# tira_rev4.net
KiCad netlist of a schematic drawn in EAGLE
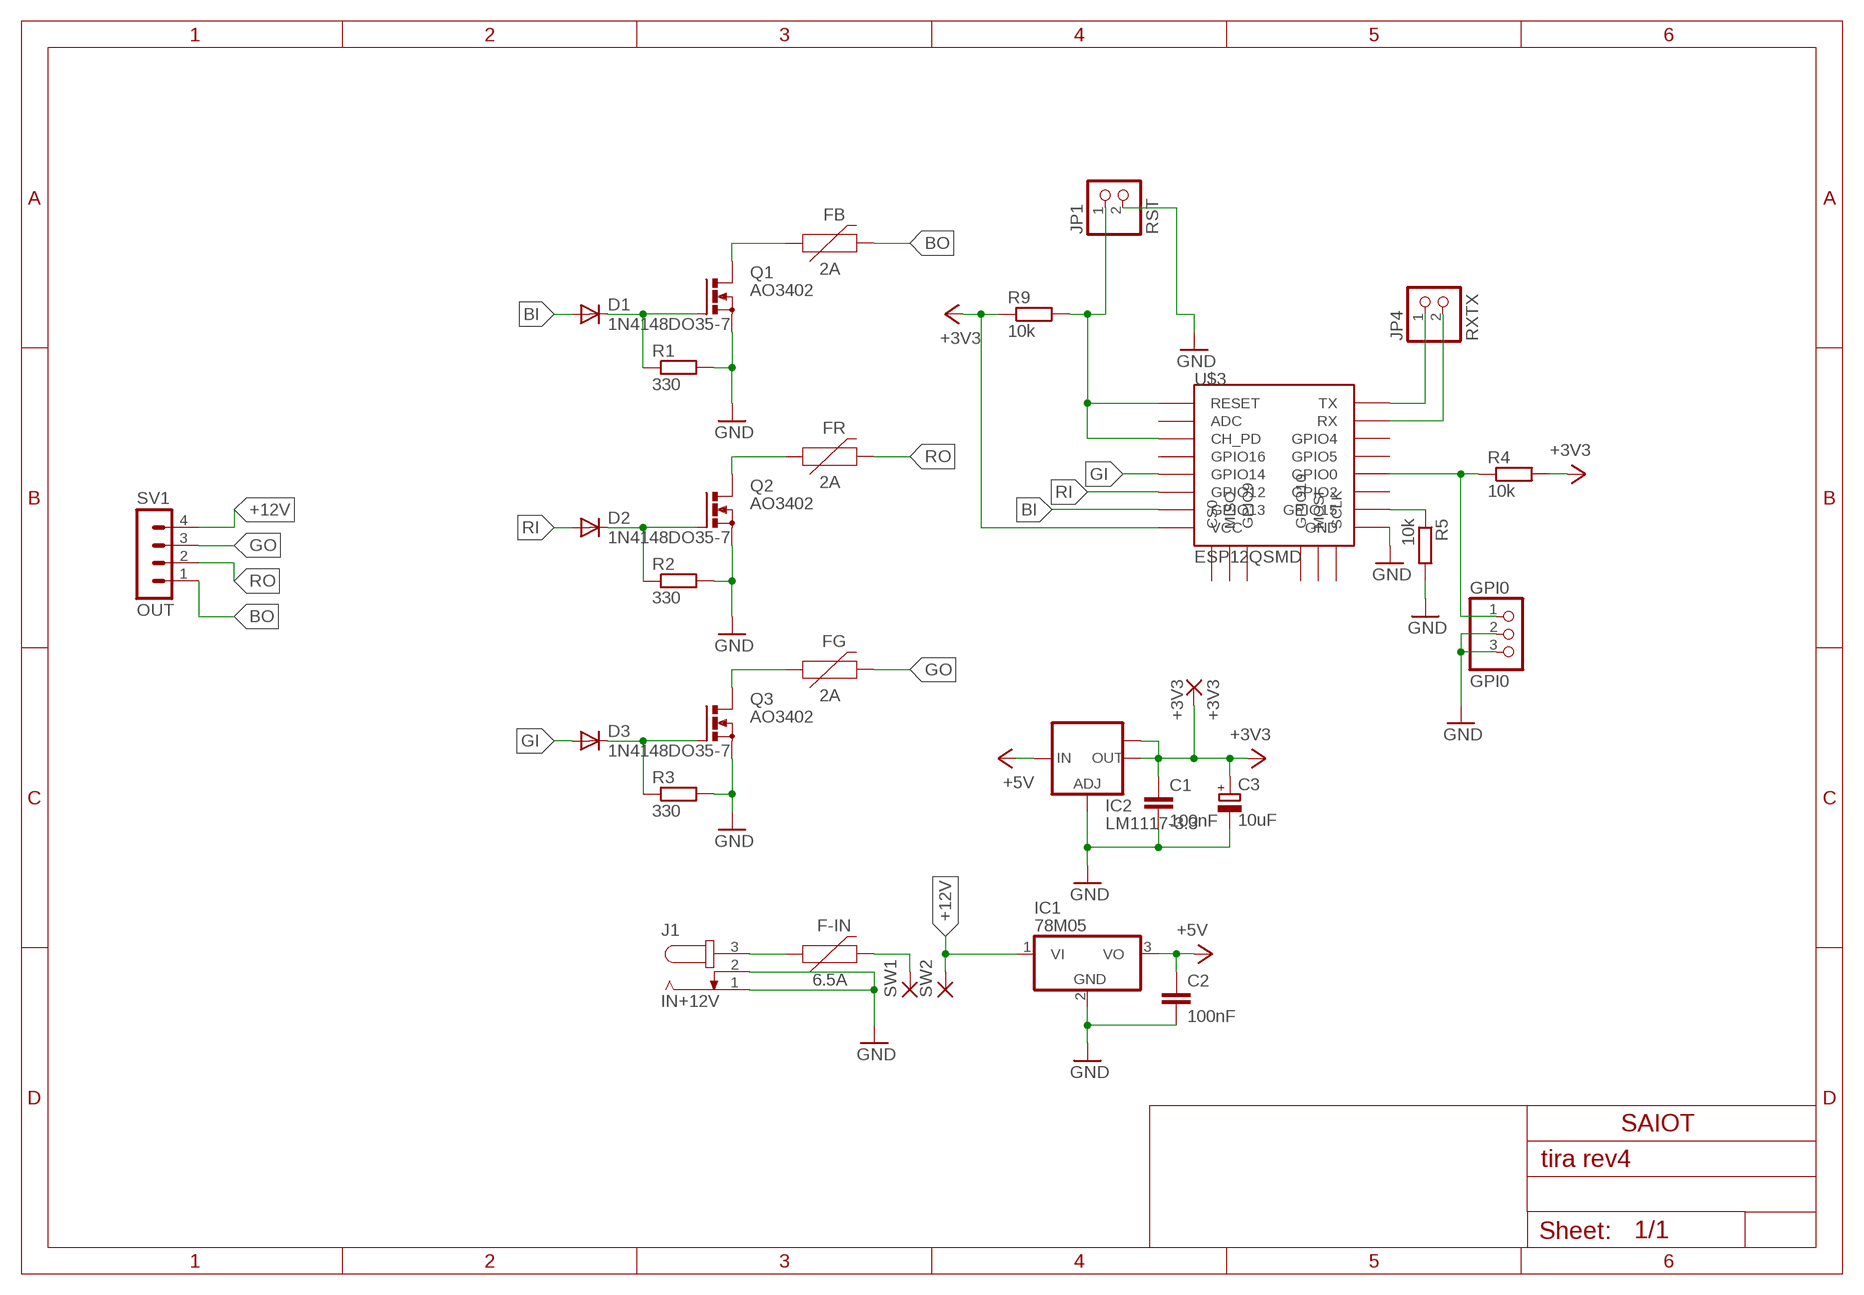
[diagram p0: schematic, sheet 1]

(export (version "E")
  (design (tool "Eeschema 10.0.6"))
  (components
    (comp (ref "+3V3")
      (value "+3V3")
      (footprint "eagle-import:2,15_1,0")
      (libsource (lib "eagle-import") (part "2,15/1,0"))
    )
    (comp (ref "C1")
      (value "100nF")
      (footprint "eagle-import:C050-024X044")
      (libsource (lib "eagle-import") (part "C-EU050-024X044"))
    )
    (comp (ref "C2")
      (value "100nF")
      (footprint "eagle-import:C050-024X044")
      (libsource (lib "eagle-import") (part "C-EU050-024X044"))
    )
    (comp (ref "C3")
      (value "10uF")
      (footprint "eagle-import:E2,5-7")
      (libsource (lib "eagle-import") (part "CPOL-EUE2.5-7"))
    )
    (comp (ref "D1")
      (value "1N4148DO35-7")
      (footprint "eagle-import:DO35-7")
      (libsource (lib "eagle-import") (part "1N4148DO35-7"))
    )
    (comp (ref "D2")
      (value "1N4148DO35-7")
      (footprint "eagle-import:DO35-7")
      (libsource (lib "eagle-import") (part "1N4148DO35-7"))
    )
    (comp (ref "D3")
      (value "1N4148DO35-7")
      (footprint "eagle-import:DO35-7")
      (libsource (lib "eagle-import") (part "1N4148DO35-7"))
    )
    (comp (ref "F-IN")
      (value "6.5A")
      (footprint "eagle-import:0805")
      (libsource (lib "eagle-import") (part "PPTC_6V500MA"))
    )
    (comp (ref "FB")
      (value "2A")
      (footprint "eagle-import:0805")
      (libsource (lib "eagle-import") (part "PPTC_6V500MA"))
    )
    (comp (ref "FG")
      (value "2A")
      (footprint "eagle-import:0805")
      (libsource (lib "eagle-import") (part "PPTC_6V500MA"))
    )
    (comp (ref "FR")
      (value "2A")
      (footprint "eagle-import:0805")
      (libsource (lib "eagle-import") (part "PPTC_6V500MA"))
    )
    (comp (ref "GPI0")
      (value "GPI0")
      (footprint "eagle-import:1X03")
      (libsource (lib "eagle-import") (part "PINHD-1X3"))
    )
    (comp (ref "IC1")
      (value "78M05")
      (footprint "eagle-import:TO220H")
      (libsource (lib "eagle-import") (part "78T05"))
    )
    (comp (ref "IC2")
      (value "LM1117-3.3")
      (footprint "eagle-import:SOT223")
      (libsource (lib "eagle-import") (part "LM1117IMPX-ADJ"))
    )
    (comp (ref "J1")
      (value "IN+12V")
      (footprint "eagle-import:SPC4077")
      (libsource (lib "eagle-import") (part "JACK-PLUG0"))
    )
    (comp (ref "JP1")
      (value "RST")
      (footprint "eagle-import:1X02")
      (libsource (lib "eagle-import") (part "PINHD-1X2"))
    )
    (comp (ref "JP4")
      (value "RXTX")
      (footprint "eagle-import:1X02")
      (libsource (lib "eagle-import") (part "PINHD-1X2"))
    )
    (comp (ref "Q1")
      (value "AO3402")
      (footprint "eagle-import:SOT-23")
      (libsource (lib "eagle-import") (part "IRLML6344"))
    )
    (comp (ref "Q2")
      (value "AO3402")
      (footprint "eagle-import:SOT-23")
      (libsource (lib "eagle-import") (part "IRLML6344"))
    )
    (comp (ref "Q3")
      (value "AO3402")
      (footprint "eagle-import:SOT-23")
      (libsource (lib "eagle-import") (part "IRLML6344"))
    )
    (comp (ref "R1")
      (value "330")
      (footprint "eagle-import:0204_7")
      (libsource (lib "eagle-import") (part "R-EU_0204/7"))
    )
    (comp (ref "R2")
      (value "330")
      (footprint "eagle-import:0204_7")
      (libsource (lib "eagle-import") (part "R-EU_0204/7"))
    )
    (comp (ref "R3")
      (value "330")
      (footprint "eagle-import:0204_7")
      (libsource (lib "eagle-import") (part "R-EU_0204/7"))
    )
    (comp (ref "R4")
      (value "10k")
      (footprint "eagle-import:0204_7")
      (libsource (lib "eagle-import") (part "R-EU_0204/7"))
    )
    (comp (ref "R5")
      (value "10k")
      (footprint "eagle-import:0204_7")
      (libsource (lib "eagle-import") (part "R-EU_0204/7"))
    )
    (comp (ref "R9")
      (value "10k")
      (footprint "eagle-import:0204_7")
      (libsource (lib "eagle-import") (part "R-EU_0204/7"))
    )
    (comp (ref "SV1")
      (value "OUT")
      (footprint "eagle-import:MA04-1")
      (libsource (lib "eagle-import") (part "MA04-1"))
    )
    (comp (ref "SW1")
      (value "1,6/0,8")
      (footprint "eagle-import:1,6_0,8")
      (libsource (lib "eagle-import") (part "1,6/0,8"))
    )
    (comp (ref "SW2")
      (value "1,6/0,8")
      (footprint "eagle-import:1,6_0,8")
      (libsource (lib "eagle-import") (part "1,6/0,8"))
    )
    (comp (ref "U$3")
      (value "ESP12QSMD")
      (footprint "eagle-import:ESP12QSMD")
      (libsource (lib "eagle-import") (part "ESP12QSMD"))
    )
  )
  (nets
    (net (code "1") (name "+3V3") (class "Default")
      (node (ref "+3V3") (pin "1") (pinfunction "P_1") (pintype "passive"))
      (node (ref "C1") (pin "1") (pinfunction "1_1") (pintype "passive"))
      (node (ref "C3") (pin "+") (pinfunction "+_+") (pintype "passive"))
      (node (ref "IC2") (pin "2") (pinfunction "OUT_2") (pintype "passive"))
      (node (ref "IC2") (pin "TAB") (pinfunction "OUT1_TAB") (pintype "passive"))
      (node (ref "R4") (pin "2") (pinfunction "2_2") (pintype "passive"))
      (node (ref "R9") (pin "1") (pinfunction "1_1") (pintype "passive"))
      (node (ref "U$3") (pin "VCC") (pinfunction "VCC_VCC") (pintype "bidirectional"))
    )
    (net (code "2") (name "+5V") (class "Default")
      (node (ref "C2") (pin "1") (pinfunction "1_1") (pintype "passive"))
      (node (ref "IC1") (pin "3") (pinfunction "VO_3") (pintype "passive"))
      (node (ref "IC2") (pin "3") (pinfunction "IN_3") (pintype "input"))
    )
    (net (code "3") (name "+12V") (class "Default")
      (node (ref "IC1") (pin "1") (pinfunction "VI_1") (pintype "input"))
      (node (ref "SV1") (pin "4") (pinfunction "4_4") (pintype "passive"))
      (node (ref "SW2") (pin "1") (pinfunction "P_1") (pintype "passive"))
    )
    (net (code "4") (name "BI") (class "Default")
      (node (ref "D1") (pin "A") (pinfunction "A_A") (pintype "passive"))
      (node (ref "U$3") (pin "GPIO13") (pinfunction "GPIO13_GPIO13") (pintype "bidirectional"))
    )
    (net (code "5") (name "BO") (class "Default")
      (node (ref "FB") (pin "2") (pinfunction "2_2") (pintype "bidirectional"))
      (node (ref "SV1") (pin "1") (pinfunction "1_1") (pintype "passive"))
    )
    (net (code "6") (name "GI") (class "Default")
      (node (ref "D3") (pin "A") (pinfunction "A_A") (pintype "passive"))
      (node (ref "U$3") (pin "GPIO14") (pinfunction "GPIO14_GPIO14") (pintype "bidirectional"))
    )
    (net (code "7") (name "GND") (class "Default")
      (node (ref "C1") (pin "2") (pinfunction "2_2") (pintype "passive"))
      (node (ref "C2") (pin "2") (pinfunction "2_2") (pintype "passive"))
      (node (ref "C3") (pin "-") (pinfunction "-_-") (pintype "passive"))
      (node (ref "GPI0") (pin "2") (pinfunction "2_2") (pintype "passive"))
      (node (ref "GPI0") (pin "3") (pinfunction "3_3") (pintype "passive"))
      (node (ref "IC1") (pin "2") (pinfunction "GND_2") (pintype "passive"))
      (node (ref "IC2") (pin "1") (pinfunction "ADJ_1") (pintype "input"))
      (node (ref "J1") (pin "1") (pinfunction "1_1") (pintype "passive"))
      (node (ref "J1") (pin "2") (pinfunction "2_2") (pintype "passive"))
      (node (ref "JP1") (pin "2") (pinfunction "2_2") (pintype "passive"))
      (node (ref "Q1") (pin "P2") (pinfunction "S_P2") (pintype "passive"))
      (node (ref "Q2") (pin "P2") (pinfunction "S_P2") (pintype "passive"))
      (node (ref "Q3") (pin "P2") (pinfunction "S_P2") (pintype "passive"))
      (node (ref "R1") (pin "2") (pinfunction "2_2") (pintype "passive"))
      (node (ref "R2") (pin "2") (pinfunction "2_2") (pintype "passive"))
      (node (ref "R3") (pin "2") (pinfunction "2_2") (pintype "passive"))
      (node (ref "R5") (pin "2") (pinfunction "2_2") (pintype "passive"))
      (node (ref "U$3") (pin "GND") (pinfunction "GND_GND") (pintype "bidirectional"))
    )
    (net (code "8") (name "GO") (class "Default")
      (node (ref "FG") (pin "2") (pinfunction "2_2") (pintype "bidirectional"))
      (node (ref "SV1") (pin "3") (pinfunction "3_3") (pintype "passive"))
    )
    (net (code "9") (name "Net-(F-IN-Pad1)") (class "Default")
      (node (ref "F-IN") (pin "1") (pinfunction "1_1") (pintype "bidirectional"))
      (node (ref "J1") (pin "3") (pinfunction "3_3") (pintype "passive"))
    )
    (net (code "10") (name "Net-(GPI0-Pad1)") (class "Default")
      (node (ref "GPI0") (pin "1") (pinfunction "1_1") (pintype "passive"))
      (node (ref "R4") (pin "1") (pinfunction "1_1") (pintype "passive"))
      (node (ref "U$3") (pin "GPIO0") (pinfunction "GPIO0_GPIO0") (pintype "bidirectional"))
    )
    (net (code "11") (name "Net-(JP1-Pad1)") (class "Default")
      (node (ref "JP1") (pin "1") (pinfunction "1_1") (pintype "passive"))
      (node (ref "R9") (pin "2") (pinfunction "2_2") (pintype "passive"))
      (node (ref "U$3") (pin "CH_PD") (pinfunction "CH_PD_CH_PD") (pintype "bidirectional"))
      (node (ref "U$3") (pin "RESET") (pinfunction "RESET_RESET") (pintype "bidirectional"))
    )
    (net (code "12") (name "Net-(JP4-Pad1)") (class "Default")
      (node (ref "JP4") (pin "1") (pinfunction "1_1") (pintype "passive"))
      (node (ref "U$3") (pin "TX") (pinfunction "TX_TX") (pintype "bidirectional"))
    )
    (net (code "13") (name "Net-(JP4-Pad2)") (class "Default")
      (node (ref "JP4") (pin "2") (pinfunction "2_2") (pintype "passive"))
      (node (ref "U$3") (pin "RX") (pinfunction "RX_RX") (pintype "bidirectional"))
    )
    (net (code "14") (name "Net-(Q1-D)") (class "Default")
      (node (ref "FB") (pin "1") (pinfunction "1_1") (pintype "bidirectional"))
      (node (ref "Q1") (pin "P3") (pinfunction "D_P3") (pintype "passive"))
    )
    (net (code "15") (name "Net-(Q1-G)") (class "Default")
      (node (ref "D1") (pin "C") (pinfunction "C_C") (pintype "passive"))
      (node (ref "Q1") (pin "P1") (pinfunction "G_P1") (pintype "passive"))
      (node (ref "R1") (pin "1") (pinfunction "1_1") (pintype "passive"))
    )
    (net (code "16") (name "Net-(Q2-D)") (class "Default")
      (node (ref "FR") (pin "1") (pinfunction "1_1") (pintype "bidirectional"))
      (node (ref "Q2") (pin "P3") (pinfunction "D_P3") (pintype "passive"))
    )
    (net (code "17") (name "Net-(Q2-G)") (class "Default")
      (node (ref "D2") (pin "C") (pinfunction "C_C") (pintype "passive"))
      (node (ref "Q2") (pin "P1") (pinfunction "G_P1") (pintype "passive"))
      (node (ref "R2") (pin "1") (pinfunction "1_1") (pintype "passive"))
    )
    (net (code "18") (name "Net-(Q3-D)") (class "Default")
      (node (ref "FG") (pin "1") (pinfunction "1_1") (pintype "bidirectional"))
      (node (ref "Q3") (pin "P3") (pinfunction "D_P3") (pintype "passive"))
    )
    (net (code "19") (name "Net-(Q3-G)") (class "Default")
      (node (ref "D3") (pin "C") (pinfunction "C_C") (pintype "passive"))
      (node (ref "Q3") (pin "P1") (pinfunction "G_P1") (pintype "passive"))
      (node (ref "R3") (pin "1") (pinfunction "1_1") (pintype "passive"))
    )
    (net (code "20") (name "Net-(R5-Pad1)") (class "Default")
      (node (ref "R5") (pin "1") (pinfunction "1_1") (pintype "passive"))
      (node (ref "U$3") (pin "GPIO15") (pinfunction "GPIO15_GPIO15") (pintype "bidirectional"))
    )
    (net (code "21") (name "Net-(SW1-P)") (class "Default")
      (node (ref "F-IN") (pin "2") (pinfunction "2_2") (pintype "bidirectional"))
      (node (ref "SW1") (pin "1") (pinfunction "P_1") (pintype "passive"))
    )
    (net (code "22") (name "RI") (class "Default")
      (node (ref "D2") (pin "A") (pinfunction "A_A") (pintype "passive"))
      (node (ref "U$3") (pin "GPIO12") (pinfunction "GPIO12_GPIO12") (pintype "bidirectional"))
    )
    (net (code "23") (name "RO") (class "Default")
      (node (ref "FR") (pin "2") (pinfunction "2_2") (pintype "bidirectional"))
      (node (ref "SV1") (pin "2") (pinfunction "2_2") (pintype "passive"))
    )
    (net (code "24") (name "unconnected-(U$3-PadADC)") (class "Default")
      (node (ref "U$3") (pin "ADC") (pinfunction "ADC_ADC") (pintype "bidirectional"))
    )
    (net (code "25") (name "unconnected-(U$3-PadCS0)") (class "Default")
      (node (ref "U$3") (pin "CS0") (pinfunction "CS0_CS0") (pintype "bidirectional"))
    )
    (net (code "26") (name "unconnected-(U$3-PadGPIO2)") (class "Default")
      (node (ref "U$3") (pin "GPIO2") (pinfunction "GPIO2_GPIO2") (pintype "bidirectional"))
    )
    (net (code "27") (name "unconnected-(U$3-PadGPIO4)") (class "Default")
      (node (ref "U$3") (pin "GPIO4") (pinfunction "GPIO4_GPIO4") (pintype "bidirectional"))
    )
    (net (code "28") (name "unconnected-(U$3-PadGPIO5)") (class "Default")
      (node (ref "U$3") (pin "GPIO5") (pinfunction "GPIO5_GPIO5") (pintype "bidirectional"))
    )
    (net (code "29") (name "unconnected-(U$3-PadGPIO9)") (class "Default")
      (node (ref "U$3") (pin "GPIO9") (pinfunction "GPIO9_GPIO9") (pintype "bidirectional"))
    )
    (net (code "30") (name "unconnected-(U$3-PadGPIO10)") (class "Default")
      (node (ref "U$3") (pin "GPIO10") (pinfunction "GPIO10_GPIO10") (pintype "bidirectional"))
    )
    (net (code "31") (name "unconnected-(U$3-PadGPIO16)") (class "Default")
      (node (ref "U$3") (pin "GPIO16") (pinfunction "GPIO16_GPIO16") (pintype "bidirectional"))
    )
    (net (code "32") (name "unconnected-(U$3-PadMISO)") (class "Default")
      (node (ref "U$3") (pin "MISO") (pinfunction "MISO_MISO") (pintype "bidirectional"))
    )
    (net (code "33") (name "unconnected-(U$3-PadMOSI)") (class "Default")
      (node (ref "U$3") (pin "MOSI") (pinfunction "MOSI_MOSI") (pintype "bidirectional"))
    )
    (net (code "34") (name "unconnected-(U$3-PadSCLK)") (class "Default")
      (node (ref "U$3") (pin "SCLK") (pinfunction "SCLK_SCLK") (pintype "bidirectional"))
    )
  )
)
